# mach_ve.net
KiCad netlist of a schematic drawn in Altium Designer
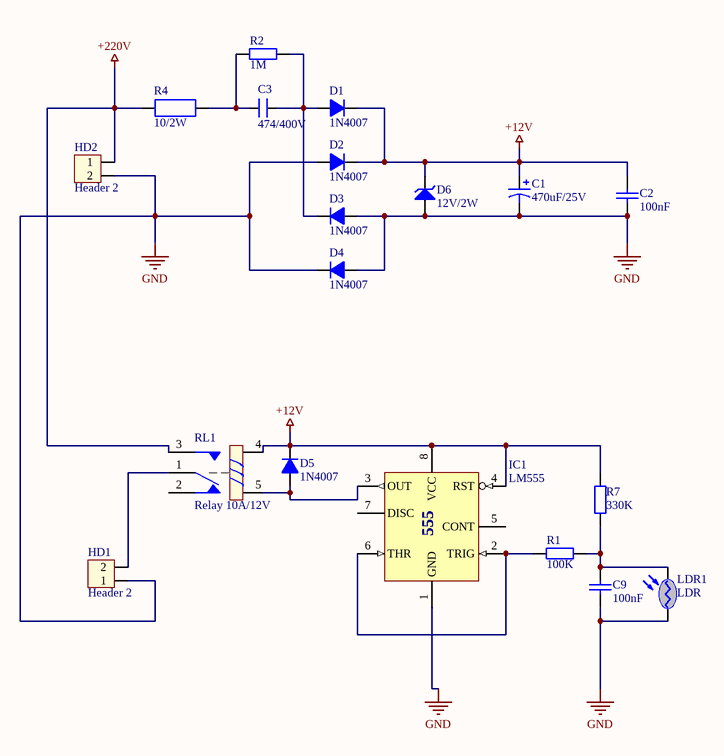
[diagram p0: mach_ve.SchDoc]

(export (version "E")
  (design (tool "Eeschema 10.0.6"))
  (components
    (comp (ref "C1")
      (value "470uF/25V")
      (footprint "C10mm")
      (description "Polarized Capacitor (Axial)")
      (fields (field (name "PUBLISHER") "Altium Limited"))
      (libsource (lib "CHN_Library") (part "Cap Pol 12mm"))
    )
    (comp (ref "C2")
      (value "100nF")
      (footprint "Tu-pico")
      (description "Capacitor")
      (fields (field (name "Comment") "Capacitor Ceramic") (field (name "PUBLISHER") "Altium Limited"))
      (libsource (lib "CHN_Library") (part "CapCeramic"))
    )
    (comp (ref "C3")
      (value "474/400V")
      (footprint "CN4")
      (description "Cap np W0.4")
      (libsource (lib "CHN_Library") (part "CN4"))
    )
    (comp (ref "C9")
      (value "100nF")
      (footprint "Tu-pico")
      (description "Capacitor")
      (fields (field (name "Comment") "Capacitor Ceramic") (field (name "PUBLISHER") "Altium Limited"))
      (libsource (lib "CHN_Library") (part "CapCeramic"))
    )
    (comp (ref "D1")
      (value "1N4007")
      (footprint "D1A")
      (description "Diode 1A")
      (libsource (lib "CHN_Library") (part "D1A"))
    )
    (comp (ref "D2")
      (value "1N4007")
      (footprint "D1A")
      (description "Diode 1A")
      (libsource (lib "CHN_Library") (part "D1A"))
    )
    (comp (ref "D3")
      (value "1N4007")
      (footprint "D1A")
      (description "Diode 1A")
      (libsource (lib "CHN_Library") (part "D1A"))
    )
    (comp (ref "D4")
      (value "1N4007")
      (footprint "D1A")
      (description "Diode 1A")
      (libsource (lib "CHN_Library") (part "D1A"))
    )
    (comp (ref "D5")
      (value "1N4007")
      (footprint "D1A")
      (description "Diode 1A")
      (libsource (lib "CHN_Library") (part "D1A"))
    )
    (comp (ref "D6")
      (value "12V/2W")
      (footprint "DIODE_ZENER")
      (description "Zener Diode")
      (fields (field (name "PUBLISHER") "Altium Limited"))
      (libsource (lib "CHN_Library") (part "Diode Zener"))
    )
    (comp (ref "HD1")
      (value "Header 2")
      (footprint "HED2")
      (description "Header 2 (Green)")
      (libsource (lib "") (part "Hed2_1"))
    )
    (comp (ref "HD2")
      (value "Header 2")
      (footprint "HED2")
      (description "Header 2 (Green)")
      (libsource (lib "CHN_Library") (part "Hed2"))
    )
    (comp (ref "IC1")
      (value "LM555")
      (footprint "DIP8/W0.3")
      (description "Timer")
      (libsource (lib "CHN_Library") (part "LM555"))
    )
    (comp (ref "LDR1")
      (value "LDR")
      (footprint "CDS")
      (description "Quang Tro")
      (libsource (lib "Compiled_Devzone") (part "LDR"))
    )
    (comp (ref "R1")
      (value "100K")
      (footprint "DIEN TRO 1/4 W")
      (description "Resistor")
      (fields (field (name "Comment") "R0.4W") (field (name "PUBLISHER") "Altium Limited"))
      (libsource (lib "CHN_Library") (part "Res 1/4 W"))
    )
    (comp (ref "R2")
      (value "1M")
      (footprint "DIEN TRO 1/4 W")
      (description "Resistor")
      (fields (field (name "Comment") "R0.4W") (field (name "PUBLISHER") "Altium Limited"))
      (libsource (lib "") (part "Res 1/4 W_1"))
    )
    (comp (ref "R4")
      (value "10/2W")
      (footprint "R2W")
      (description "Resistor 2W")
      (libsource (lib "CHN_Library") (part "R2W"))
    )
    (comp (ref "R7")
      (value "330K")
      (footprint "DIEN TRO 1/4 W")
      (description "Resistor")
      (fields (field (name "Comment") "R0.4W") (field (name "PUBLISHER") "Altium Limited"))
      (libsource (lib "") (part "Res 1/4 W_2"))
    )
    (comp (ref "RL1")
      (value "Relay 10A/12V")
      (footprint "RL_SPDT_10A")
      (description "Relay SPDT,10A - 12VDC 5 Pin")
      (libsource (lib "CHN_Library") (part "Relay 1"))
    )
  )
  (nets
    (net (code "1") (name "+12V") (class "Default")
      (node (ref "C1") (pin "1") (pinfunction "1_1") (pintype "passive"))
      (node (ref "C2") (pin "2") (pinfunction "2_2") (pintype "passive"))
      (node (ref "D1") (pin "2") (pinfunction "K_2") (pintype "passive"))
      (node (ref "D2") (pin "2") (pinfunction "K_2") (pintype "passive"))
      (node (ref "D5") (pin "2") (pinfunction "K_2") (pintype "passive"))
      (node (ref "D6") (pin "2") (pinfunction "K_2") (pintype "passive"))
      (node (ref "IC1") (pin "4") (pinfunction "RST_4") (pintype "input"))
      (node (ref "IC1") (pin "8") (pinfunction "VCC_8") (pintype "power_in"))
      (node (ref "R7") (pin "2") (pinfunction "2_2") (pintype "passive"))
      (node (ref "RL1") (pin "4") (pinfunction "4_4") (pintype "passive"))
    )
    (net (code "2") (name "+220V") (class "Default")
      (node (ref "HD2") (pin "1") (pinfunction "1_1") (pintype "passive"))
      (node (ref "R4") (pin "1") (pinfunction "1_1") (pintype "passive"))
      (node (ref "RL1") (pin "3") (pinfunction "3_3") (pintype "passive"))
    )
    (net (code "3") (name "GND") (class "Default")
      (node (ref "C1") (pin "2") (pinfunction "2_2") (pintype "passive"))
      (node (ref "C2") (pin "1") (pinfunction "1_1") (pintype "passive"))
      (node (ref "C9") (pin "1") (pinfunction "1_1") (pintype "passive"))
      (node (ref "D2") (pin "1") (pinfunction "A_1") (pintype "passive"))
      (node (ref "D3") (pin "1") (pinfunction "A_1") (pintype "passive"))
      (node (ref "D4") (pin "1") (pinfunction "A_1") (pintype "passive"))
      (node (ref "D4") (pin "2") (pinfunction "K_2") (pintype "passive"))
      (node (ref "D6") (pin "1") (pinfunction "A_1") (pintype "passive"))
      (node (ref "HD1") (pin "1") (pinfunction "1_1") (pintype "passive"))
      (node (ref "HD2") (pin "2") (pinfunction "2_2") (pintype "passive"))
      (node (ref "IC1") (pin "1") (pinfunction "GND_1") (pintype "power_in"))
      (node (ref "LDR1") (pin "1") (pinfunction "A_1") (pintype "passive"))
    )
    (net (code "4") (name "Net-(C3-Pad1)") (class "Default")
      (node (ref "C3") (pin "1") (pinfunction "1_1") (pintype "passive"))
      (node (ref "R2") (pin "2") (pinfunction "2_2") (pintype "passive"))
      (node (ref "R4") (pin "2") (pinfunction "2_2") (pintype "passive"))
    )
    (net (code "5") (name "Net-(D1-A)") (class "Default")
      (node (ref "C3") (pin "2") (pinfunction "2_2") (pintype "passive"))
      (node (ref "D1") (pin "1") (pinfunction "A_1") (pintype "passive"))
      (node (ref "D3") (pin "2") (pinfunction "K_2") (pintype "passive"))
      (node (ref "R2") (pin "1") (pinfunction "1_1") (pintype "passive"))
    )
    (net (code "6") (name "Net-(D5-A)") (class "Default")
      (node (ref "D5") (pin "1") (pinfunction "A_1") (pintype "passive"))
      (node (ref "IC1") (pin "3") (pinfunction "OUT_3") (pintype "output"))
      (node (ref "RL1") (pin "5") (pinfunction "5_5") (pintype "passive"))
    )
    (net (code "7") (name "Net-(HD1-Pad2)") (class "Default")
      (node (ref "HD1") (pin "2") (pinfunction "2_2") (pintype "passive"))
      (node (ref "RL1") (pin "1") (pinfunction "1_1") (pintype "passive"))
    )
    (net (code "8") (name "Net-(IC1-THR)") (class "Default")
      (node (ref "IC1") (pin "2") (pinfunction "TRIG_2") (pintype "input"))
      (node (ref "IC1") (pin "6") (pinfunction "THR_6") (pintype "input"))
      (node (ref "R1") (pin "1") (pinfunction "1_1") (pintype "passive"))
    )
    (net (code "9") (name "Net-(LDR1-K)") (class "Default")
      (node (ref "C9") (pin "2") (pinfunction "2_2") (pintype "passive"))
      (node (ref "LDR1") (pin "2") (pinfunction "K_2") (pintype "passive"))
      (node (ref "R1") (pin "2") (pinfunction "2_2") (pintype "passive"))
      (node (ref "R7") (pin "1") (pinfunction "1_1") (pintype "passive"))
    )
    (net (code "10") (name "unconnected-(IC1-CONT-Pad5)") (class "Default")
      (node (ref "IC1") (pin "5") (pinfunction "CONT_5") (pintype "passive"))
    )
    (net (code "11") (name "unconnected-(IC1-DISC-Pad7)") (class "Default")
      (node (ref "IC1") (pin "7") (pinfunction "DISC_7") (pintype "open_collector"))
    )
    (net (code "12") (name "unconnected-(RL1-Pad2)") (class "Default")
      (node (ref "RL1") (pin "2") (pinfunction "2_2") (pintype "passive"))
    )
  )
)
